# Heater_Driver.net
KiCad netlist of a schematic drawn in Altium Designer
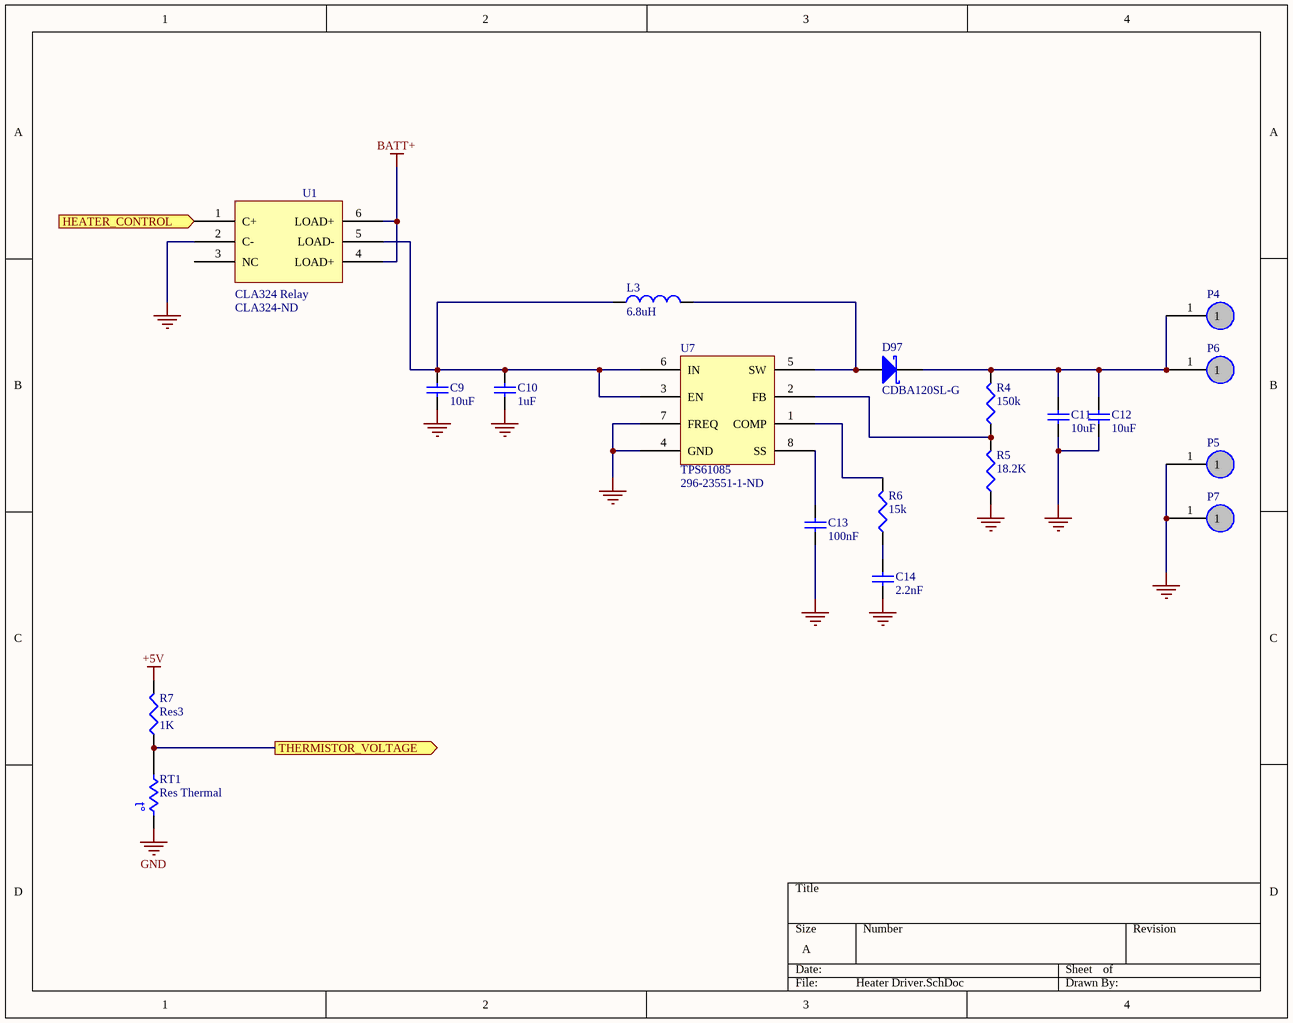
[diagram p0: Heater Driver.SchDoc]

(export (version "E")
  (design (tool "Eeschema 10.0.6"))
  (components
    (comp (ref "C9")
      (value "10uF")
      (footprint "CAPC3216L")
      (description "Capacitor (Semiconductor SIM Model)")
      (fields (field (name "Comment") "Cap Semi") (field (name "PUBLISHER") "Altium Limited"))
      (libsource (lib "Miscellaneous Devices") (part "Cap Semi"))
    )
    (comp (ref "C10")
      (value "1uF")
      (footprint "CAPC3216L")
      (description "Capacitor (Semiconductor SIM Model)")
      (fields (field (name "Comment") "Cap Semi") (field (name "PUBLISHER") "Altium Limited"))
      (libsource (lib "Miscellaneous Devices") (part "Cap Semi"))
    )
    (comp (ref "C11")
      (value "10uF")
      (footprint "CAPC3216L")
      (description "Capacitor (Semiconductor SIM Model)")
      (fields (field (name "Comment") "Cap Semi") (field (name "PUBLISHER") "Altium Limited"))
      (libsource (lib "Miscellaneous Devices") (part "Cap Semi"))
    )
    (comp (ref "C12")
      (value "10uF")
      (footprint "CAPC3216L")
      (description "Capacitor (Semiconductor SIM Model)")
      (fields (field (name "Comment") "Cap Semi") (field (name "PUBLISHER") "Altium Limited"))
      (libsource (lib "Miscellaneous Devices") (part "Cap Semi"))
    )
    (comp (ref "C13")
      (value "100nF")
      (footprint "CAPC3216L")
      (description "Capacitor (Semiconductor SIM Model)")
      (fields (field (name "Comment") "Cap Semi") (field (name "PUBLISHER") "Altium Limited"))
      (libsource (lib "Miscellaneous Devices") (part "Cap Semi"))
    )
    (comp (ref "C14")
      (value "2.2nF")
      (footprint "CAPC3216L")
      (description "Capacitor (Semiconductor SIM Model)")
      (fields (field (name "Comment") "Cap Semi") (field (name "PUBLISHER") "Altium Limited"))
      (libsource (lib "Miscellaneous Devices") (part "Cap Semi"))
    )
    (comp (ref "D97")
      (value "CDBA120SL-G")
      (footprint "DSO-C2/G1.6")
      (fields (field (name "PUBLISHER") "Altium Limited"))
      (libsource (lib "Miscellaneous Devices") (part "Diode BAS70"))
    )
    (comp (ref "L3")
      (value "6.8uH")
      (footprint "MURATA SMT INDUCTOR")
      (description "Inductor")
      (fields (field (name "PUBLISHER") "Altium Limited"))
      (libsource (lib "Miscellaneous Devices") (part "Inductor"))
    )
    (comp (ref "P4")
      (value "LARGE_PIN")
      (footprint "2.5mm PIN")
      (libsource (lib "Altium Footprints") (part "LARGE_PIN"))
    )
    (comp (ref "P5")
      (value "LARGE_PIN")
      (footprint "2.5mm PIN")
      (libsource (lib "Altium Footprints") (part "LARGE_PIN"))
    )
    (comp (ref "P6")
      (value "LARGE_PIN")
      (footprint "2.5mm PIN")
      (libsource (lib "Altium Footprints") (part "LARGE_PIN"))
    )
    (comp (ref "P7")
      (value "LARGE_PIN")
      (footprint "2.5mm PIN")
      (libsource (lib "Altium Footprints") (part "LARGE_PIN"))
    )
    (comp (ref "R4")
      (value "150k")
      (footprint "RESC3216L")
      (description "Resistor")
      (fields (field (name "Comment") "Res3") (field (name "PUBLISHER") "Altium Limited"))
      (libsource (lib "Miscellaneous Devices") (part "Res3"))
    )
    (comp (ref "R5")
      (value "18.2K")
      (footprint "RESC3216L")
      (description "Resistor")
      (fields (field (name "Comment") "Res3") (field (name "PUBLISHER") "Altium Limited"))
      (libsource (lib "Miscellaneous Devices") (part "Res3"))
    )
    (comp (ref "R6")
      (value "15k")
      (footprint "RESC3216L")
      (description "Resistor")
      (fields (field (name "Comment") "Res3") (field (name "PUBLISHER") "Altium Limited"))
      (libsource (lib "Miscellaneous Devices") (part "Res3"))
    )
    (comp (ref "R7")
      (value "Res3")
      (footprint "RESC3216M")
      (description "Resistor")
      (fields (field (name "ALTIUM_VALUE") "1K") (field (name "PUBLISHER") "Altium Limited"))
      (libsource (lib "Miscellaneous Devices") (part "Res3"))
    )
    (comp (ref "RT1")
      (value "Res Thermal")
      (footprint "2MM JST PH - 2 PIN")
      (description "Thermistor")
      (fields (field (name "PUBLISHER") "Altium Limited"))
      (libsource (lib "Miscellaneous Devices") (part "Res Thermal"))
    )
    (comp (ref "U1")
      (value "CLA324 Relay")
      (footprint "6-SMD")
      (fields (field (name "SUPPLIER PART NUMBER 1") "CLA324-ND"))
      (libsource (lib "Altium Footprints") (part "CLA324 Relay"))
    )
    (comp (ref "U7")
      (value "TPS61085")
      (footprint "DB008")
      (fields (field (name "SUPPLIER PART NUMBER 1") "296-23551-1-ND"))
      (libsource (lib "Altium Footprints") (part "TPS61085"))
    )
  )
  (nets
    (net (code "1") (name "+5V") (class "Default")
      (node (ref "R7") (pin "2") (pinfunction "2_2") (pintype "passive"))
    )
    (net (code "2") (name "/HEATER_CONTROL") (class "Default")
      (node (ref "U1") (pin "1") (pinfunction "C+_1") (pintype "passive"))
    )
    (net (code "3") (name "/THERMISTOR_VOLTAGE") (class "Default")
      (node (ref "R7") (pin "1") (pinfunction "1_1") (pintype "passive"))
      (node (ref "RT1") (pin "2") (pinfunction "2_2") (pintype "passive"))
    )
    (net (code "4") (name "BATT+") (class "Default")
      (node (ref "U1") (pin "4") (pinfunction "LOAD+_4") (pintype "passive"))
      (node (ref "U1") (pin "6") (pinfunction "LOAD+_6") (pintype "passive"))
    )
    (net (code "5") (name "GND") (class "Default")
      (node (ref "C10") (pin "1") (pinfunction "1_1") (pintype "passive"))
      (node (ref "C11") (pin "1") (pinfunction "1_1") (pintype "passive"))
      (node (ref "C12") (pin "1") (pinfunction "1_1") (pintype "passive"))
      (node (ref "C13") (pin "1") (pinfunction "1_1") (pintype "passive"))
      (node (ref "C14") (pin "1") (pinfunction "1_1") (pintype "passive"))
      (node (ref "C9") (pin "1") (pinfunction "1_1") (pintype "passive"))
      (node (ref "P5") (pin "1") (pinfunction "1_1") (pintype "passive"))
      (node (ref "P7") (pin "1") (pinfunction "1_1") (pintype "passive"))
      (node (ref "R5") (pin "1") (pinfunction "1_1") (pintype "passive"))
      (node (ref "U1") (pin "2") (pinfunction "C-_2") (pintype "passive"))
      (node (ref "U7") (pin "4") (pinfunction "GND_4") (pintype "passive"))
      (node (ref "U7") (pin "7") (pinfunction "FREQ_7") (pintype "passive"))
    )
    (net (code "6") (name "Net-(C14-Pad2)") (class "Default")
      (node (ref "C14") (pin "2") (pinfunction "2_2") (pintype "passive"))
      (node (ref "R6") (pin "1") (pinfunction "1_1") (pintype "passive"))
    )
    (net (code "7") (name "Net-(D97-A)") (class "Default")
      (node (ref "D97") (pin "1") (pinfunction "A_1") (pintype "passive"))
      (node (ref "L3") (pin "2") (pinfunction "2_2") (pintype "passive"))
      (node (ref "U7") (pin "5") (pinfunction "SW_5") (pintype "passive"))
    )
    (net (code "8") (name "Net-(D97-K)") (class "Default")
      (node (ref "C11") (pin "2") (pinfunction "2_2") (pintype "passive"))
      (node (ref "C12") (pin "2") (pinfunction "2_2") (pintype "passive"))
      (node (ref "D97") (pin "2") (pinfunction "K_2") (pintype "passive"))
      (node (ref "P4") (pin "1") (pinfunction "1_1") (pintype "passive"))
      (node (ref "P6") (pin "1") (pinfunction "1_1") (pintype "passive"))
      (node (ref "R4") (pin "2") (pinfunction "2_2") (pintype "passive"))
    )
    (net (code "9") (name "Net-(U1-LOAD-)") (class "Default")
      (node (ref "C10") (pin "2") (pinfunction "2_2") (pintype "passive"))
      (node (ref "C9") (pin "2") (pinfunction "2_2") (pintype "passive"))
      (node (ref "L3") (pin "1") (pinfunction "1_1") (pintype "passive"))
      (node (ref "U1") (pin "5") (pinfunction "LOAD-_5") (pintype "passive"))
      (node (ref "U7") (pin "3") (pinfunction "EN_3") (pintype "passive"))
      (node (ref "U7") (pin "6") (pinfunction "IN_6") (pintype "passive"))
    )
    (net (code "10") (name "Net-(U7-COMP)") (class "Default")
      (node (ref "R6") (pin "2") (pinfunction "2_2") (pintype "passive"))
      (node (ref "U7") (pin "1") (pinfunction "COMP_1") (pintype "passive"))
    )
    (net (code "11") (name "Net-(U7-FB)") (class "Default")
      (node (ref "R4") (pin "1") (pinfunction "1_1") (pintype "passive"))
      (node (ref "R5") (pin "2") (pinfunction "2_2") (pintype "passive"))
      (node (ref "U7") (pin "2") (pinfunction "FB_2") (pintype "passive"))
    )
    (net (code "12") (name "Net-(U7-SS)") (class "Default")
      (node (ref "C13") (pin "2") (pinfunction "2_2") (pintype "passive"))
      (node (ref "U7") (pin "8") (pinfunction "SS_8") (pintype "passive"))
    )
    (net (code "13") (name "unconnected-(RT1-Pad1)") (class "Default")
      (node (ref "RT1") (pin "1") (pinfunction "1_1") (pintype "passive"))
    )
    (net (code "14") (name "unconnected-(U1-NC-Pad3)") (class "Default")
      (node (ref "U1") (pin "3") (pinfunction "NC_3") (pintype "passive"))
    )
  )
)
